# 08_FPGA.net
KiCad netlist of a schematic drawn in Altium Designer
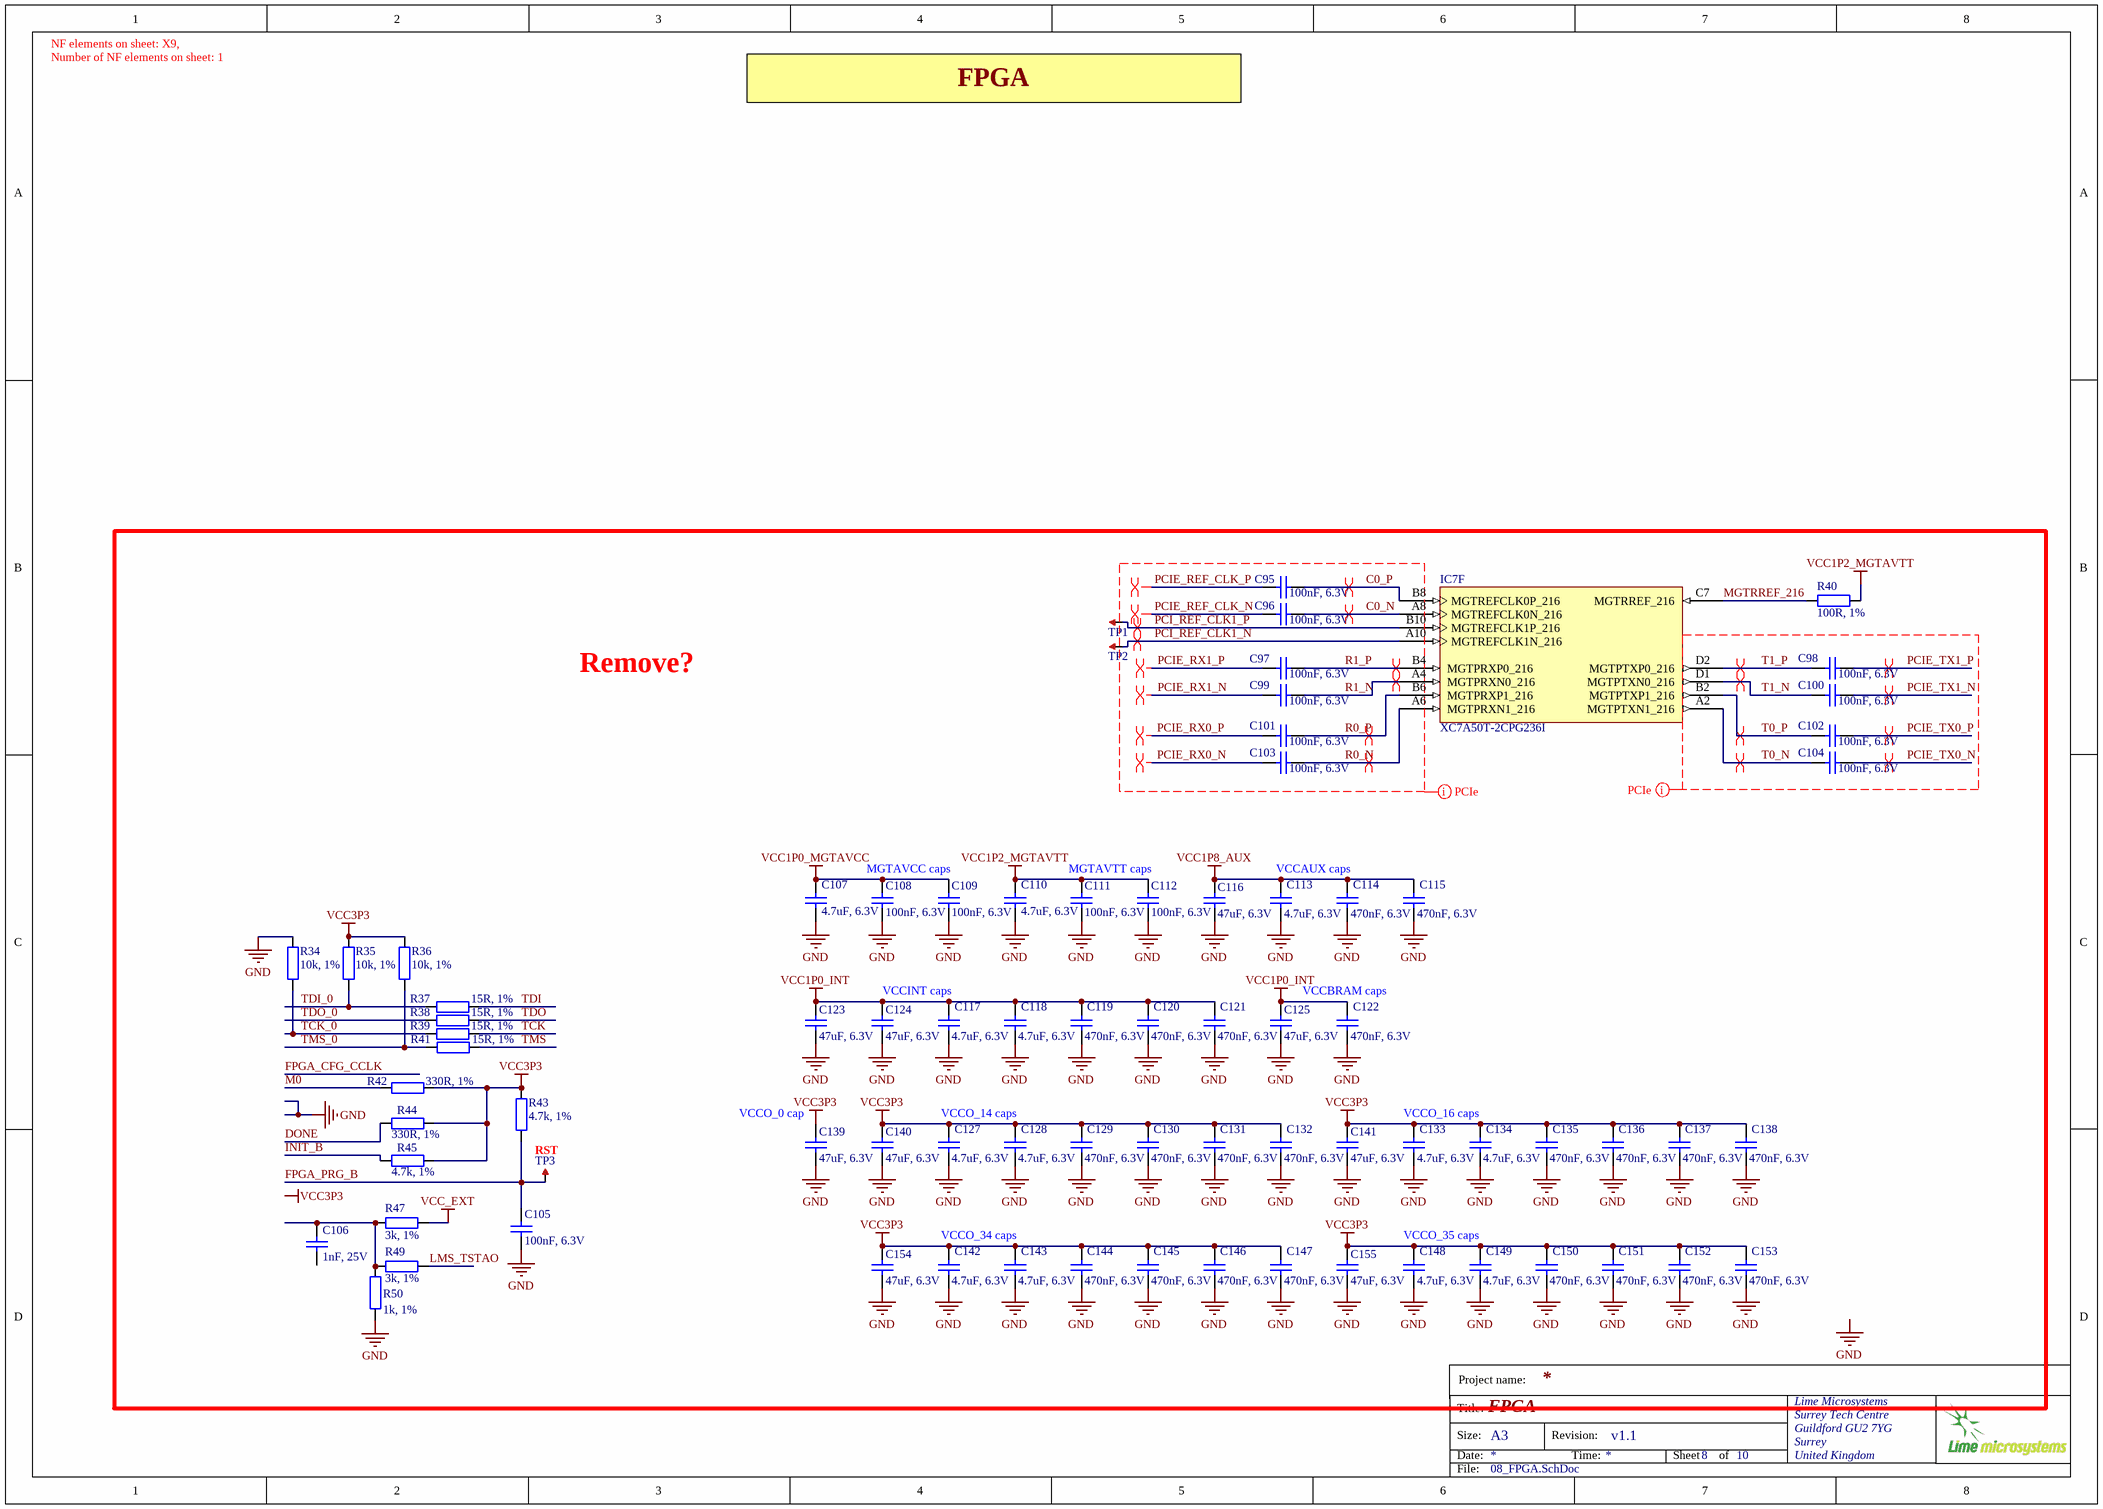
[diagram p0: 08_FPGA.SchDoc]

(export (version "E")
  (design (tool "Eeschema 10.0.6"))
  (components
    (comp (ref "C95")
      (value "100nF, 6.3V")
      (footprint "CAP0201")
      (fields (field (name "MANUFACTURER") "Samsung") (field (name "TOLERANCE") "20%"))
      (libsource (lib "LimeMicroAltiumLib_schLib") (part "Cap_0402"))
    )
    (comp (ref "C96")
      (value "100nF, 6.3V")
      (footprint "CAP0201")
      (fields (field (name "MANUFACTURER") "Samsung") (field (name "TOLERANCE") "20%"))
      (libsource (lib "LimeMicroAltiumLib_schLib") (part "Cap_0402"))
    )
    (comp (ref "C97")
      (value "100nF, 6.3V")
      (footprint "CAP0201")
      (fields (field (name "MANUFACTURER") "Samsung") (field (name "TOLERANCE") "20%"))
      (libsource (lib "LimeMicroAltiumLib_schLib") (part "Cap_0402"))
    )
    (comp (ref "C98")
      (value "100nF, 6.3V")
      (footprint "CAP0201")
      (fields (field (name "MANUFACTURER") "Samsung") (field (name "TOLERANCE") "20%"))
      (libsource (lib "LimeMicroAltiumLib_schLib") (part "Cap_0402"))
    )
    (comp (ref "C99")
      (value "100nF, 6.3V")
      (footprint "CAP0201")
      (fields (field (name "MANUFACTURER") "Samsung") (field (name "TOLERANCE") "20%"))
      (libsource (lib "LimeMicroAltiumLib_schLib") (part "Cap_0402"))
    )
    (comp (ref "C100")
      (value "100nF, 6.3V")
      (footprint "CAP0201")
      (fields (field (name "MANUFACTURER") "Samsung") (field (name "TOLERANCE") "20%"))
      (libsource (lib "LimeMicroAltiumLib_schLib") (part "Cap_0402"))
    )
    (comp (ref "C101")
      (value "100nF, 6.3V")
      (footprint "CAP0201")
      (fields (field (name "MANUFACTURER") "Samsung") (field (name "TOLERANCE") "20%"))
      (libsource (lib "LimeMicroAltiumLib_schLib") (part "Cap_0402"))
    )
    (comp (ref "C102")
      (value "100nF, 6.3V")
      (footprint "CAP0201")
      (fields (field (name "MANUFACTURER") "Samsung") (field (name "TOLERANCE") "20%"))
      (libsource (lib "LimeMicroAltiumLib_schLib") (part "Cap_0402"))
    )
    (comp (ref "C103")
      (value "100nF, 6.3V")
      (footprint "CAP0201")
      (fields (field (name "MANUFACTURER") "Samsung") (field (name "TOLERANCE") "20%"))
      (libsource (lib "LimeMicroAltiumLib_schLib") (part "Cap_0402"))
    )
    (comp (ref "C104")
      (value "100nF, 6.3V")
      (footprint "CAP0201")
      (fields (field (name "MANUFACTURER") "Samsung") (field (name "TOLERANCE") "20%"))
      (libsource (lib "LimeMicroAltiumLib_schLib") (part "Cap_0402"))
    )
    (comp (ref "C105")
      (value "100nF, 6.3V")
      (footprint "CAP0201")
      (fields (field (name "MANUFACTURER") "Samsung") (field (name "TOLERANCE") "20%"))
      (libsource (lib "LimeMicroAltiumLib_schLib") (part "Cap_0402"))
    )
    (comp (ref "C106")
      (value "1nF, 25V")
      (footprint "CAP0201")
      (fields (field (name "TOLERANCE") "±10%") (field (name "MANUFACTURER") "TDK Corporation"))
      (libsource (lib "LimeMicroAltiumLib_schLib") (part "Cap_0402"))
    )
    (comp (ref "C107")
      (value "4.7uF, 6.3V")
      (footprint "CAP0402")
      (fields
        (field (name "MANUFACTURER") "Murata Electronics North America")
        (field (name "TOLERANCE") "±20%")
      )
      (libsource (lib "LimeMicroAltiumLib_schLib") (part "Cap_0402"))
    )
    (comp (ref "C108")
      (value "100nF, 6.3V")
      (footprint "CAP0201")
      (fields (field (name "MANUFACTURER") "Samsung") (field (name "TOLERANCE") "20%"))
      (libsource (lib "LimeMicroAltiumLib_schLib") (part "Cap_0402"))
    )
    (comp (ref "C109")
      (value "100nF, 6.3V")
      (footprint "CAP0201")
      (fields (field (name "MANUFACTURER") "Samsung") (field (name "TOLERANCE") "20%"))
      (libsource (lib "LimeMicroAltiumLib_schLib") (part "Cap_0402"))
    )
    (comp (ref "C110")
      (value "4.7uF, 6.3V")
      (footprint "CAP0402")
      (fields
        (field (name "MANUFACTURER") "Murata Electronics North America")
        (field (name "TOLERANCE") "±20%")
      )
      (libsource (lib "LimeMicroAltiumLib_schLib") (part "Cap_0402"))
    )
    (comp (ref "C111")
      (value "100nF, 6.3V")
      (footprint "CAP0201")
      (fields (field (name "MANUFACTURER") "Samsung") (field (name "TOLERANCE") "20%"))
      (libsource (lib "LimeMicroAltiumLib_schLib") (part "Cap_0402"))
    )
    (comp (ref "C112")
      (value "100nF, 6.3V")
      (footprint "CAP0201")
      (fields (field (name "MANUFACTURER") "Samsung") (field (name "TOLERANCE") "20%"))
      (libsource (lib "LimeMicroAltiumLib_schLib") (part "Cap_0402"))
    )
    (comp (ref "C113")
      (value "4.7uF, 6.3V")
      (footprint "CAP0402")
      (fields
        (field (name "MANUFACTURER") "Murata Electronics North America")
        (field (name "TOLERANCE") "±20%")
      )
      (libsource (lib "LimeMicroAltiumLib_schLib") (part "Cap_0402"))
    )
    (comp (ref "C114")
      (value "470nF, 6.3V")
      (footprint "CAP0201")
      (fields (field (name "MANUFACTURER") "Murata") (field (name "TOLERANCE") "10%"))
      (libsource (lib "LimeMicroAltiumLib_schLib") (part "Cap_0402"))
    )
    (comp (ref "C115")
      (value "470nF, 6.3V")
      (footprint "CAP0201")
      (fields (field (name "MANUFACTURER") "Murata") (field (name "TOLERANCE") "10%"))
      (libsource (lib "LimeMicroAltiumLib_schLib") (part "Cap_0402"))
    )
    (comp (ref "C116")
      (value "47uF, 6.3V")
      (footprint "CAP0603")
      (fields (field (name "MANUFACTURER") "Murata") (field (name "TOLERANCE") "20%"))
      (libsource (lib "LimeFPGAboard_schLib") (part "Cap_0603"))
    )
    (comp (ref "C117")
      (value "4.7uF, 6.3V")
      (footprint "CAP0402")
      (fields
        (field (name "MANUFACTURER") "Murata Electronics North America")
        (field (name "TOLERANCE") "±20%")
      )
      (libsource (lib "LimeMicroAltiumLib_schLib") (part "Cap_0402"))
    )
    (comp (ref "C118")
      (value "4.7uF, 6.3V")
      (footprint "CAP0402")
      (fields
        (field (name "MANUFACTURER") "Murata Electronics North America")
        (field (name "TOLERANCE") "±20%")
      )
      (libsource (lib "LimeMicroAltiumLib_schLib") (part "Cap_0402"))
    )
    (comp (ref "C119")
      (value "470nF, 6.3V")
      (footprint "CAP0201")
      (fields (field (name "MANUFACTURER") "Murata") (field (name "TOLERANCE") "10%"))
      (libsource (lib "LimeMicroAltiumLib_schLib") (part "Cap_0402"))
    )
    (comp (ref "C120")
      (value "470nF, 6.3V")
      (footprint "CAP0201")
      (fields (field (name "MANUFACTURER") "Murata") (field (name "TOLERANCE") "10%"))
      (libsource (lib "LimeMicroAltiumLib_schLib") (part "Cap_0402"))
    )
    (comp (ref "C121")
      (value "470nF, 6.3V")
      (footprint "CAP0201")
      (fields (field (name "MANUFACTURER") "Murata") (field (name "TOLERANCE") "10%"))
      (libsource (lib "LimeMicroAltiumLib_schLib") (part "Cap_0402"))
    )
    (comp (ref "C122")
      (value "470nF, 6.3V")
      (footprint "CAP0201")
      (fields (field (name "MANUFACTURER") "Murata") (field (name "TOLERANCE") "10%"))
      (libsource (lib "LimeMicroAltiumLib_schLib") (part "Cap_0402"))
    )
    (comp (ref "C123")
      (value "47uF, 6.3V")
      (footprint "CAP0603")
      (fields (field (name "MANUFACTURER") "Murata") (field (name "TOLERANCE") "20%"))
      (libsource (lib "LimeFPGAboard_schLib") (part "Cap_0603"))
    )
    (comp (ref "C124")
      (value "47uF, 6.3V")
      (footprint "CAP0603")
      (fields (field (name "MANUFACTURER") "Murata") (field (name "TOLERANCE") "20%"))
      (libsource (lib "LimeFPGAboard_schLib") (part "Cap_0603"))
    )
    (comp (ref "C125")
      (value "47uF, 6.3V")
      (footprint "CAP0603")
      (fields (field (name "MANUFACTURER") "Murata") (field (name "TOLERANCE") "20%"))
      (libsource (lib "LimeFPGAboard_schLib") (part "Cap_0603"))
    )
    (comp (ref "C127")
      (value "4.7uF, 6.3V")
      (footprint "CAP0402")
      (fields
        (field (name "MANUFACTURER") "Murata Electronics North America")
        (field (name "TOLERANCE") "±20%")
      )
      (libsource (lib "LimeMicroAltiumLib_schLib") (part "Cap_0402"))
    )
    (comp (ref "C128")
      (value "4.7uF, 6.3V")
      (footprint "CAP0402")
      (fields
        (field (name "MANUFACTURER") "Murata Electronics North America")
        (field (name "TOLERANCE") "±20%")
      )
      (libsource (lib "LimeMicroAltiumLib_schLib") (part "Cap_0402"))
    )
    (comp (ref "C129")
      (value "470nF, 6.3V")
      (footprint "CAP0201")
      (fields (field (name "MANUFACTURER") "Murata") (field (name "TOLERANCE") "10%"))
      (libsource (lib "LimeMicroAltiumLib_schLib") (part "Cap_0402"))
    )
    (comp (ref "C130")
      (value "470nF, 6.3V")
      (footprint "CAP0201")
      (fields (field (name "MANUFACTURER") "Murata") (field (name "TOLERANCE") "10%"))
      (libsource (lib "LimeMicroAltiumLib_schLib") (part "Cap_0402"))
    )
    (comp (ref "C131")
      (value "470nF, 6.3V")
      (footprint "CAP0201")
      (fields (field (name "MANUFACTURER") "Murata") (field (name "TOLERANCE") "10%"))
      (libsource (lib "LimeMicroAltiumLib_schLib") (part "Cap_0402"))
    )
    (comp (ref "C132")
      (value "470nF, 6.3V")
      (footprint "CAP0201")
      (fields (field (name "MANUFACTURER") "Murata") (field (name "TOLERANCE") "10%"))
      (libsource (lib "LimeMicroAltiumLib_schLib") (part "Cap_0402"))
    )
    (comp (ref "C133")
      (value "4.7uF, 6.3V")
      (footprint "CAP0402")
      (fields
        (field (name "MANUFACTURER") "Murata Electronics North America")
        (field (name "TOLERANCE") "±20%")
      )
      (libsource (lib "LimeMicroAltiumLib_schLib") (part "Cap_0402"))
    )
    (comp (ref "C134")
      (value "4.7uF, 6.3V")
      (footprint "CAP0402")
      (fields
        (field (name "MANUFACTURER") "Murata Electronics North America")
        (field (name "TOLERANCE") "±20%")
      )
      (libsource (lib "LimeMicroAltiumLib_schLib") (part "Cap_0402"))
    )
    (comp (ref "C135")
      (value "470nF, 6.3V")
      (footprint "CAP0201")
      (fields (field (name "MANUFACTURER") "Murata") (field (name "TOLERANCE") "10%"))
      (libsource (lib "LimeMicroAltiumLib_schLib") (part "Cap_0402"))
    )
    (comp (ref "C136")
      (value "470nF, 6.3V")
      (footprint "CAP0201")
      (fields (field (name "MANUFACTURER") "Murata") (field (name "TOLERANCE") "10%"))
      (libsource (lib "LimeMicroAltiumLib_schLib") (part "Cap_0402"))
    )
    (comp (ref "C137")
      (value "470nF, 6.3V")
      (footprint "CAP0201")
      (fields (field (name "MANUFACTURER") "Murata") (field (name "TOLERANCE") "10%"))
      (libsource (lib "LimeMicroAltiumLib_schLib") (part "Cap_0402"))
    )
    (comp (ref "C138")
      (value "470nF, 6.3V")
      (footprint "CAP0201")
      (fields (field (name "MANUFACTURER") "Murata") (field (name "TOLERANCE") "10%"))
      (libsource (lib "LimeMicroAltiumLib_schLib") (part "Cap_0402"))
    )
    (comp (ref "C139")
      (value "47uF, 6.3V")
      (footprint "CAP0603")
      (fields (field (name "MANUFACTURER") "Murata") (field (name "TOLERANCE") "20%"))
      (libsource (lib "LimeFPGAboard_schLib") (part "Cap_0603"))
    )
    (comp (ref "C140")
      (value "47uF, 6.3V")
      (footprint "CAP0603")
      (fields (field (name "MANUFACTURER") "Murata") (field (name "TOLERANCE") "20%"))
      (libsource (lib "LimeFPGAboard_schLib") (part "Cap_0603"))
    )
    (comp (ref "C141")
      (value "47uF, 6.3V")
      (footprint "CAP0603")
      (fields (field (name "MANUFACTURER") "Murata") (field (name "TOLERANCE") "20%"))
      (libsource (lib "LimeFPGAboard_schLib") (part "Cap_0603"))
    )
    (comp (ref "C142")
      (value "4.7uF, 6.3V")
      (footprint "CAP0402")
      (fields
        (field (name "MANUFACTURER") "Murata Electronics North America")
        (field (name "TOLERANCE") "±20%")
      )
      (libsource (lib "LimeMicroAltiumLib_schLib") (part "Cap_0402"))
    )
    (comp (ref "C143")
      (value "4.7uF, 6.3V")
      (footprint "CAP0402")
      (fields
        (field (name "MANUFACTURER") "Murata Electronics North America")
        (field (name "TOLERANCE") "±20%")
      )
      (libsource (lib "LimeMicroAltiumLib_schLib") (part "Cap_0402"))
    )
    (comp (ref "C144")
      (value "470nF, 6.3V")
      (footprint "CAP0201")
      (fields (field (name "MANUFACTURER") "Murata") (field (name "TOLERANCE") "10%"))
      (libsource (lib "LimeMicroAltiumLib_schLib") (part "Cap_0402"))
    )
    (comp (ref "C145")
      (value "470nF, 6.3V")
      (footprint "CAP0201")
      (fields (field (name "MANUFACTURER") "Murata") (field (name "TOLERANCE") "10%"))
      (libsource (lib "LimeMicroAltiumLib_schLib") (part "Cap_0402"))
    )
    (comp (ref "C146")
      (value "470nF, 6.3V")
      (footprint "CAP0201")
      (fields (field (name "MANUFACTURER") "Murata") (field (name "TOLERANCE") "10%"))
      (libsource (lib "LimeMicroAltiumLib_schLib") (part "Cap_0402"))
    )
    (comp (ref "C147")
      (value "470nF, 6.3V")
      (footprint "CAP0201")
      (fields (field (name "MANUFACTURER") "Murata") (field (name "TOLERANCE") "10%"))
      (libsource (lib "LimeMicroAltiumLib_schLib") (part "Cap_0402"))
    )
    (comp (ref "C148")
      (value "4.7uF, 6.3V")
      (footprint "CAP0402")
      (fields
        (field (name "MANUFACTURER") "Murata Electronics North America")
        (field (name "TOLERANCE") "±20%")
      )
      (libsource (lib "LimeMicroAltiumLib_schLib") (part "Cap_0402"))
    )
    (comp (ref "C149")
      (value "4.7uF, 6.3V")
      (footprint "CAP0402")
      (fields
        (field (name "MANUFACTURER") "Murata Electronics North America")
        (field (name "TOLERANCE") "±20%")
      )
      (libsource (lib "LimeMicroAltiumLib_schLib") (part "Cap_0402"))
    )
    (comp (ref "C150")
      (value "470nF, 6.3V")
      (footprint "CAP0201")
      (fields (field (name "MANUFACTURER") "Murata") (field (name "TOLERANCE") "10%"))
      (libsource (lib "LimeMicroAltiumLib_schLib") (part "Cap_0402"))
    )
    (comp (ref "C151")
      (value "470nF, 6.3V")
      (footprint "CAP0201")
      (fields (field (name "MANUFACTURER") "Murata") (field (name "TOLERANCE") "10%"))
      (libsource (lib "LimeMicroAltiumLib_schLib") (part "Cap_0402"))
    )
    (comp (ref "C152")
      (value "470nF, 6.3V")
      (footprint "CAP0201")
      (fields (field (name "MANUFACTURER") "Murata") (field (name "TOLERANCE") "10%"))
      (libsource (lib "LimeMicroAltiumLib_schLib") (part "Cap_0402"))
    )
    (comp (ref "C153")
      (value "470nF, 6.3V")
      (footprint "CAP0201")
      (fields (field (name "MANUFACTURER") "Murata") (field (name "TOLERANCE") "10%"))
      (libsource (lib "LimeMicroAltiumLib_schLib") (part "Cap_0402"))
    )
    (comp (ref "C154")
      (value "47uF, 6.3V")
      (footprint "CAP0603")
      (fields (field (name "MANUFACTURER") "Murata") (field (name "TOLERANCE") "20%"))
      (libsource (lib "LimeFPGAboard_schLib") (part "Cap_0603"))
    )
    (comp (ref "C155")
      (value "47uF, 6.3V")
      (footprint "CAP0603")
      (fields (field (name "MANUFACTURER") "Murata") (field (name "TOLERANCE") "20%"))
      (libsource (lib "LimeFPGAboard_schLib") (part "Cap_0603"))
    )
    (comp (ref "IC7")
      (value "XC7A50T-2CPG236I")
      (footprint "XC7A35T-2CPG236")
      (description "Artix-7 FPGA")
      (fields (field (name "MANUFACTURER") "Xilinx"))
      (libsource (lib "LimeMicroAltiumLib_schLib_r04") (part "XC7A35T-2CPG236"))
    )
    (comp (ref "R34")
      (value "10k, 1%")
      (footprint "RES0201")
      (fields (field (name "MANUFACTURER") "Yageo") (field (name "TOLERANCE") "1%"))
      (libsource (lib "LimeFPGAboard_schLib") (part "Res_0402"))
    )
    (comp (ref "R35")
      (value "10k, 1%")
      (footprint "RES0201")
      (fields (field (name "MANUFACTURER") "Yageo") (field (name "TOLERANCE") "1%"))
      (libsource (lib "LimeFPGAboard_schLib") (part "Res_0402"))
    )
    (comp (ref "R36")
      (value "10k, 1%")
      (footprint "RES0201")
      (fields (field (name "MANUFACTURER") "Yageo") (field (name "TOLERANCE") "1%"))
      (libsource (lib "LimeFPGAboard_schLib") (part "Res_0402"))
    )
    (comp (ref "R37")
      (value "15R, 1%")
      (footprint "RES0201")
      (fields (field (name "MANUFACTURER") "Yageo") (field (name "TOLERANCE") "1%"))
      (libsource (lib "LimeFPGAboard_schLib") (part "Res_0402"))
    )
    (comp (ref "R38")
      (value "15R, 1%")
      (footprint "RES0201")
      (fields (field (name "MANUFACTURER") "Yageo") (field (name "TOLERANCE") "1%"))
      (libsource (lib "LimeFPGAboard_schLib") (part "Res_0402"))
    )
    (comp (ref "R39")
      (value "15R, 1%")
      (footprint "RES0201")
      (fields (field (name "MANUFACTURER") "Yageo") (field (name "TOLERANCE") "1%"))
      (libsource (lib "LimeFPGAboard_schLib") (part "Res_0402"))
    )
    (comp (ref "R40")
      (value "100R, 1%")
      (footprint "RES0201")
      (fields (field (name "MANUFACTURER") "Yageo") (field (name "TOLERANCE") "1%"))
      (libsource (lib "LimeFPGAboard_schLib") (part "Res_0402"))
    )
    (comp (ref "R41")
      (value "15R, 1%")
      (footprint "RES0201")
      (fields (field (name "MANUFACTURER") "Yageo") (field (name "TOLERANCE") "1%"))
      (libsource (lib "LimeFPGAboard_schLib") (part "Res_0402"))
    )
    (comp (ref "R42")
      (value "330R, 1%")
      (footprint "RES0201")
      (fields (field (name "MANUFACTURER") "Vishay Dale") (field (name "TOLERANCE") "1%"))
      (libsource (lib "LimeFPGAboard_schLib") (part "Res_0402"))
    )
    (comp (ref "R43")
      (value "4.7k, 1%")
      (footprint "RES0201")
      (fields (field (name "MANUFACTURER") "Yageo") (field (name "TOLERANCE") "1%"))
      (libsource (lib "LimeFPGAboard_schLib") (part "Res_0402"))
    )
    (comp (ref "R44")
      (value "330R, 1%")
      (footprint "RES0201")
      (fields (field (name "MANUFACTURER") "Vishay Dale") (field (name "TOLERANCE") "1%"))
      (libsource (lib "LimeFPGAboard_schLib") (part "Res_0402"))
    )
    (comp (ref "R45")
      (value "4.7k, 1%")
      (footprint "RES0201")
      (fields (field (name "MANUFACTURER") "Yageo") (field (name "TOLERANCE") "1%"))
      (libsource (lib "LimeFPGAboard_schLib") (part "Res_0402"))
    )
    (comp (ref "R47")
      (value "3k, 1%")
      (footprint "RES0201")
      (fields (field (name "MANUFACTURER") "Yageo") (field (name "TOLERANCE") "1%"))
      (libsource (lib "LimeFPGAboard_schLib") (part "Res_0402"))
    )
    (comp (ref "R49")
      (value "3k, 1%")
      (footprint "RES0201")
      (fields (field (name "MANUFACTURER") "Yageo") (field (name "TOLERANCE") "1%"))
      (libsource (lib "LimeFPGAboard_schLib") (part "Res_0402"))
    )
    (comp (ref "R50")
      (value "1k, 1%")
      (footprint "RES0201")
      (fields (field (name "MANUFACTURER") "Yageo") (field (name "TOLERANCE") "1%"))
      (libsource (lib "LimeMicroAltiumLib_schLib") (part "Res_0402"))
    )
    (comp (ref "TP1")
      (value "TESTPOINT_PAD")
      (footprint "TP_PAD_1MM")
      (description "Test Point PCB mount Miniature White")
      (libsource (lib "LimeMicroAltiumLib_schLib_r04") (part "TESTPOINT_PAD"))
    )
    (comp (ref "TP2")
      (value "TESTPOINT_PAD")
      (footprint "TP_PAD_1MM")
      (description "Test Point PCB mount Miniature White")
      (libsource (lib "LimeMicroAltiumLib_schLib_r04") (part "TESTPOINT_PAD"))
    )
    (comp (ref "TP3")
      (value "TESTPOINT_PAD")
      (footprint "TP_PAD_1MM")
      (description "Test Point PCB mount Miniature White")
      (libsource (lib "LimeMicroAltiumLib_schLib_r04") (part "TESTPOINT_PAD"))
    )
  )
  (nets
    (net (code "1") (name "/C0_N") (class "Default")
      (node (ref "C96") (pin "2") (pinfunction "2_2") (pintype "passive"))
      (node (ref "IC7") (pin "A8") (pinfunction "MGTREFCLK0N_216_A8") (pintype "input"))
    )
    (net (code "2") (name "/C0_P") (class "Default")
      (node (ref "C95") (pin "2") (pinfunction "2_2") (pintype "passive"))
      (node (ref "IC7") (pin "B8") (pinfunction "MGTREFCLK0P_216_B8") (pintype "input"))
    )
    (net (code "3") (name "/DONE") (class "Default")
      (node (ref "R44") (pin "2") (pinfunction "2_2") (pintype "passive"))
    )
    (net (code "5") (name "/FPGA_PRG_B") (class "Default")
      (node (ref "C105") (pin "1") (pinfunction "1_1") (pintype "passive"))
      (node (ref "R43") (pin "2") (pinfunction "2_2") (pintype "passive"))
      (node (ref "TP3") (pin "1") (pintype "passive"))
    )
    (net (code "6") (name "/INIT_B") (class "Default")
      (node (ref "R45") (pin "2") (pinfunction "2_2") (pintype "passive"))
    )
    (net (code "7") (name "/LMS_TSTAO") (class "Default")
      (node (ref "R49") (pin "2") (pinfunction "2_2") (pintype "passive"))
    )
    (net (code "8") (name "/M0") (class "Default")
      (node (ref "R42") (pin "2") (pinfunction "2_2") (pintype "passive"))
    )
    (net (code "9") (name "/MGTRREF_216") (class "Default")
      (node (ref "IC7") (pin "C7") (pinfunction "MGTRREF_216_C7") (pintype "input"))
      (node (ref "R40") (pin "2") (pinfunction "2_2") (pintype "passive"))
    )
    (net (code "10") (name "/PCIE_REF_CLK_N") (class "Default")
      (node (ref "C96") (pin "1") (pinfunction "1_1") (pintype "passive"))
    )
    (net (code "11") (name "/PCIE_REF_CLK_P") (class "Default")
      (node (ref "C95") (pin "1") (pinfunction "1_1") (pintype "passive"))
    )
    (net (code "12") (name "/PCIE_RX0_N") (class "Default")
      (node (ref "C103") (pin "1") (pinfunction "1_1") (pintype "passive"))
    )
    (net (code "13") (name "/PCIE_RX0_P") (class "Default")
      (node (ref "C101") (pin "1") (pinfunction "1_1") (pintype "passive"))
    )
    (net (code "14") (name "/PCIE_RX1_N") (class "Default")
      (node (ref "C99") (pin "1") (pinfunction "1_1") (pintype "passive"))
    )
    (net (code "15") (name "/PCIE_RX1_P") (class "Default")
      (node (ref "C97") (pin "1") (pinfunction "1_1") (pintype "passive"))
    )
    (net (code "16") (name "/PCIE_TX0_N") (class "Default")
      (node (ref "C104") (pin "2") (pinfunction "2_2") (pintype "passive"))
    )
    (net (code "17") (name "/PCIE_TX0_P") (class "Default")
      (node (ref "C102") (pin "2") (pinfunction "2_2") (pintype "passive"))
    )
    (net (code "18") (name "/PCIE_TX1_N") (class "Default")
      (node (ref "C100") (pin "2") (pinfunction "2_2") (pintype "passive"))
    )
    (net (code "19") (name "/PCIE_TX1_P") (class "Default")
      (node (ref "C98") (pin "2") (pinfunction "2_2") (pintype "passive"))
    )
    (net (code "20") (name "/PCI_REF_CLK1_N") (class "Default")
      (node (ref "IC7") (pin "A10") (pinfunction "MGTREFCLK1N_216_A10") (pintype "input"))
      (node (ref "TP2") (pin "1") (pintype "passive"))
    )
    (net (code "21") (name "/PCI_REF_CLK1_P") (class "Default")
      (node (ref "IC7") (pin "B10") (pinfunction "MGTREFCLK1P_216_B10") (pintype "input"))
      (node (ref "TP1") (pin "1") (pintype "passive"))
    )
    (net (code "22") (name "/R0_N") (class "Default")
      (node (ref "C103") (pin "2") (pinfunction "2_2") (pintype "passive"))
      (node (ref "IC7") (pin "A6") (pinfunction "MGTPRXN1_216_A6") (pintype "input"))
    )
    (net (code "23") (name "/R0_P") (class "Default")
      (node (ref "C101") (pin "2") (pinfunction "2_2") (pintype "passive"))
      (node (ref "IC7") (pin "B6") (pinfunction "MGTPRXP1_216_B6") (pintype "input"))
    )
    (net (code "24") (name "/R1_N") (class "Default")
      (node (ref "C99") (pin "2") (pinfunction "2_2") (pintype "passive"))
      (node (ref "IC7") (pin "A4") (pinfunction "MGTPRXN0_216_A4") (pintype "input"))
    )
    (net (code "25") (name "/R1_P") (class "Default")
      (node (ref "C97") (pin "2") (pinfunction "2_2") (pintype "passive"))
      (node (ref "IC7") (pin "B4") (pinfunction "MGTPRXP0_216_B4") (pintype "input"))
    )
    (net (code "26") (name "/T0_N") (class "Default")
      (node (ref "C104") (pin "1") (pinfunction "1_1") (pintype "passive"))
      (node (ref "IC7") (pin "A2") (pinfunction "MGTPTXN1_216_A2") (pintype "output"))
    )
    (net (code "27") (name "/T0_P") (class "Default")
      (node (ref "C102") (pin "1") (pinfunction "1_1") (pintype "passive"))
      (node (ref "IC7") (pin "B2") (pinfunction "MGTPTXP1_216_B2") (pintype "output"))
    )
    (net (code "28") (name "/T1_N") (class "Default")
      (node (ref "C100") (pin "1") (pinfunction "1_1") (pintype "passive"))
      (node (ref "IC7") (pin "D1") (pinfunction "MGTPTXN0_216_D1") (pintype "output"))
    )
    (net (code "29") (name "/T1_P") (class "Default")
      (node (ref "C98") (pin "1") (pinfunction "1_1") (pintype "passive"))
      (node (ref "IC7") (pin "D2") (pinfunction "MGTPTXP0_216_D2") (pintype "output"))
    )
    (net (code "30") (name "/TCK") (class "Default")
      (node (ref "R39") (pin "1") (pinfunction "1_1") (pintype "passive"))
    )
    (net (code "31") (name "/TCK_0") (class "Default")
      (node (ref "R34") (pin "2") (pinfunction "2_2") (pintype "passive"))
      (node (ref "R39") (pin "2") (pinfunction "2_2") (pintype "passive"))
    )
    (net (code "32") (name "/TDI") (class "Default")
      (node (ref "R37") (pin "1") (pinfunction "1_1") (pintype "passive"))
    )
    (net (code "33") (name "/TDI_0") (class "Default")
      (node (ref "R35") (pin "2") (pinfunction "2_2") (pintype "passive"))
      (node (ref "R37") (pin "2") (pinfunction "2_2") (pintype "passive"))
    )
    (net (code "34") (name "/TDO") (class "Default")
      (node (ref "R38") (pin "1") (pinfunction "1_1") (pintype "passive"))
    )
    (net (code "35") (name "/TDO_0") (class "Default")
      (node (ref "R38") (pin "2") (pinfunction "2_2") (pintype "passive"))
    )
    (net (code "36") (name "/TMS") (class "Default")
      (node (ref "R41") (pin "1") (pinfunction "1_1") (pintype "passive"))
    )
    (net (code "37") (name "/TMS_0") (class "Default")
      (node (ref "R36") (pin "2") (pinfunction "2_2") (pintype "passive"))
      (node (ref "R41") (pin "2") (pinfunction "2_2") (pintype "passive"))
    )
    (net (code "38") (name "GND") (class "Default")
      (node (ref "C105") (pin "2") (pinfunction "2_2") (pintype "passive"))
      (node (ref "C107") (pin "1") (pinfunction "1_1") (pintype "passive"))
      (node (ref "C108") (pin "2") (pinfunction "2_2") (pintype "passive"))
      (node (ref "C109") (pin "2") (pinfunction "2_2") (pintype "passive"))
      (node (ref "C110") (pin "1") (pinfunction "1_1") (pintype "passive"))
      (node (ref "C111") (pin "2") (pinfunction "2_2") (pintype "passive"))
      (node (ref "C112") (pin "2") (pinfunction "2_2") (pintype "passive"))
      (node (ref "C113") (pin "1") (pinfunction "1_1") (pintype "passive"))
      (node (ref "C114") (pin "2") (pinfunction "2_2") (pintype "passive"))
      (node (ref "C115") (pin "2") (pinfunction "2_2") (pintype "passive"))
      (node (ref "C116") (pin "1") (pinfunction "1_1") (pintype "passive"))
      (node (ref "C117") (pin "1") (pinfunction "1_1") (pintype "passive"))
      (node (ref "C118") (pin "1") (pinfunction "1_1") (pintype "passive"))
      (node (ref "C119") (pin "2") (pinfunction "2_2") (pintype "passive"))
      (node (ref "C120") (pin "2") (pinfunction "2_2") (pintype "passive"))
      (node (ref "C121") (pin "2") (pinfunction "2_2") (pintype "passive"))
      (node (ref "C122") (pin "2") (pinfunction "2_2") (pintype "passive"))
      (node (ref "C123") (pin "1") (pinfunction "1_1") (pintype "passive"))
      (node (ref "C124") (pin "1") (pinfunction "1_1") (pintype "passive"))
      (node (ref "C125") (pin "1") (pinfunction "1_1") (pintype "passive"))
      (node (ref "C127") (pin "1") (pinfunction "1_1") (pintype "passive"))
      (node (ref "C128") (pin "1") (pinfunction "1_1") (pintype "passive"))
      (node (ref "C129") (pin "2") (pinfunction "2_2") (pintype "passive"))
      (node (ref "C130") (pin "2") (pinfunction "2_2") (pintype "passive"))
      (node (ref "C131") (pin "2") (pinfunction "2_2") (pintype "passive"))
      (node (ref "C132") (pin "2") (pinfunction "2_2") (pintype "passive"))
      (node (ref "C133") (pin "1") (pinfunction "1_1") (pintype "passive"))
      (node (ref "C134") (pin "1") (pinfunction "1_1") (pintype "passive"))
      (node (ref "C135") (pin "2") (pinfunction "2_2") (pintype "passive"))
      (node (ref "C136") (pin "2") (pinfunction "2_2") (pintype "passive"))
      (node (ref "C137") (pin "2") (pinfunction "2_2") (pintype "passive"))
      (node (ref "C138") (pin "2") (pinfunction "2_2") (pintype "passive"))
      (node (ref "C139") (pin "1") (pinfunction "1_1") (pintype "passive"))
      (node (ref "C140") (pin "1") (pinfunction "1_1") (pintype "passive"))
      (node (ref "C141") (pin "1") (pinfunction "1_1") (pintype "passive"))
      (node (ref "C142") (pin "1") (pinfunction "1_1") (pintype "passive"))
      (node (ref "C143") (pin "1") (pinfunction "1_1") (pintype "passive"))
      (node (ref "C144") (pin "2") (pinfunction "2_2") (pintype "passive"))
      (node (ref "C145") (pin "2") (pinfunction "2_2") (pintype "passive"))
      (node (ref "C146") (pin "2") (pinfunction "2_2") (pintype "passive"))
      (node (ref "C147") (pin "2") (pinfunction "2_2") (pintype "passive"))
      (node (ref "C148") (pin "1") (pinfunction "1_1") (pintype "passive"))
      (node (ref "C149") (pin "1") (pinfunction "1_1") (pintype "passive"))
      (node (ref "C150") (pin "2") (pinfunction "2_2") (pintype "passive"))
      (node (ref "C151") (pin "2") (pinfunction "2_2") (pintype "passive"))
      (node (ref "C152") (pin "2") (pinfunction "2_2") (pintype "passive"))
      (node (ref "C153") (pin "2") (pinfunction "2_2") (pintype "passive"))
      (node (ref "C154") (pin "1") (pinfunction "1_1") (pintype "passive"))
      (node (ref "C155") (pin "1") (pinfunction "1_1") (pintype "passive"))
      (node (ref "R34") (pin "1") (pinfunction "1_1") (pintype "passive"))
      (node (ref "R50") (pin "2") (pinfunction "2_2") (pintype "passive"))
    )
    (net (code "39") (name "Net-(C106-Pad1)") (class "Default")
      (node (ref "C106") (pin "1") (pinfunction "1_1") (pintype "passive"))
      (node (ref "R47") (pin "1") (pinfunction "1_1") (pintype "passive"))
      (node (ref "R49") (pin "1") (pinfunction "1_1") (pintype "passive"))
      (node (ref "R50") (pin "1") (pinfunction "1_1") (pintype "passive"))
    )
    (net (code "40") (name "VCC1P0_INT") (class "Default")
      (node (ref "C117") (pin "2") (pinfunction "2_2") (pintype "passive"))
      (node (ref "C118") (pin "2") (pinfunction "2_2") (pintype "passive"))
      (node (ref "C119") (pin "1") (pinfunction "1_1") (pintype "passive"))
      (node (ref "C120") (pin "1") (pinfunction "1_1") (pintype "passive"))
      (node (ref "C121") (pin "1") (pinfunction "1_1") (pintype "passive"))
      (node (ref "C122") (pin "1") (pinfunction "1_1") (pintype "passive"))
      (node (ref "C123") (pin "2") (pinfunction "2_2") (pintype "passive"))
      (node (ref "C124") (pin "2") (pinfunction "2_2") (pintype "passive"))
      (node (ref "C125") (pin "2") (pinfunction "2_2") (pintype "passive"))
    )
    (net (code "41") (name "VCC1P0_MGTAVCC") (class "Default")
      (node (ref "C107") (pin "2") (pinfunction "2_2") (pintype "passive"))
      (node (ref "C108") (pin "1") (pinfunction "1_1") (pintype "passive"))
      (node (ref "C109") (pin "1") (pinfunction "1_1") (pintype "passive"))
    )
    (net (code "42") (name "VCC1P2_MGTAVTT") (class "Default")
      (node (ref "C110") (pin "2") (pinfunction "2_2") (pintype "passive"))
      (node (ref "C111") (pin "1") (pinfunction "1_1") (pintype "passive"))
      (node (ref "C112") (pin "1") (pinfunction "1_1") (pintype "passive"))
      (node (ref "R40") (pin "1") (pinfunction "1_1") (pintype "passive"))
    )
    (net (code "43") (name "VCC1P8_AUX") (class "Default")
      (node (ref "C113") (pin "2") (pinfunction "2_2") (pintype "passive"))
      (node (ref "C114") (pin "1") (pinfunction "1_1") (pintype "passive"))
      (node (ref "C115") (pin "1") (pinfunction "1_1") (pintype "passive"))
      (node (ref "C116") (pin "2") (pinfunction "2_2") (pintype "passive"))
    )
    (net (code "44") (name "VCC3P3") (class "Default")
      (node (ref "C127") (pin "2") (pinfunction "2_2") (pintype "passive"))
      (node (ref "C128") (pin "2") (pinfunction "2_2") (pintype "passive"))
      (node (ref "C129") (pin "1") (pinfunction "1_1") (pintype "passive"))
      (node (ref "C130") (pin "1") (pinfunction "1_1") (pintype "passive"))
      (node (ref "C131") (pin "1") (pinfunction "1_1") (pintype "passive"))
      (node (ref "C132") (pin "1") (pinfunction "1_1") (pintype "passive"))
      (node (ref "C133") (pin "2") (pinfunction "2_2") (pintype "passive"))
      (node (ref "C134") (pin "2") (pinfunction "2_2") (pintype "passive"))
      (node (ref "C135") (pin "1") (pinfunction "1_1") (pintype "passive"))
      (node (ref "C136") (pin "1") (pinfunction "1_1") (pintype "passive"))
      (node (ref "C137") (pin "1") (pinfunction "1_1") (pintype "passive"))
      (node (ref "C138") (pin "1") (pinfunction "1_1") (pintype "passive"))
      (node (ref "C139") (pin "2") (pinfunction "2_2") (pintype "passive"))
      (node (ref "C140") (pin "2") (pinfunction "2_2") (pintype "passive"))
      (node (ref "C141") (pin "2") (pinfunction "2_2") (pintype "passive"))
      (node (ref "C142") (pin "2") (pinfunction "2_2") (pintype "passive"))
      (node (ref "C143") (pin "2") (pinfunction "2_2") (pintype "passive"))
      (node (ref "C144") (pin "1") (pinfunction "1_1") (pintype "passive"))
      (node (ref "C145") (pin "1") (pinfunction "1_1") (pintype "passive"))
      (node (ref "C146") (pin "1") (pinfunction "1_1") (pintype "passive"))
      (node (ref "C147") (pin "1") (pinfunction "1_1") (pintype "passive"))
      (node (ref "C148") (pin "2") (pinfunction "2_2") (pintype "passive"))
      (node (ref "C149") (pin "2") (pinfunction "2_2") (pintype "passive"))
      (node (ref "C150") (pin "1") (pinfunction "1_1") (pintype "passive"))
      (node (ref "C151") (pin "1") (pinfunction "1_1") (pintype "passive"))
      (node (ref "C152") (pin "1") (pinfunction "1_1") (pintype "passive"))
      (node (ref "C153") (pin "1") (pinfunction "1_1") (pintype "passive"))
      (node (ref "C154") (pin "2") (pinfunction "2_2") (pintype "passive"))
      (node (ref "C155") (pin "2") (pinfunction "2_2") (pintype "passive"))
      (node (ref "R35") (pin "1") (pinfunction "1_1") (pintype "passive"))
      (node (ref "R36") (pin "1") (pinfunction "1_1") (pintype "passive"))
      (node (ref "R42") (pin "1") (pinfunction "1_1") (pintype "passive"))
      (node (ref "R43") (pin "1") (pinfunction "1_1") (pintype "passive"))
      (node (ref "R44") (pin "1") (pinfunction "1_1") (pintype "passive"))
      (node (ref "R45") (pin "1") (pinfunction "1_1") (pintype "passive"))
    )
    (net (code "45") (name "VCC_EXT") (class "Default")
      (node (ref "R47") (pin "2") (pinfunction "2_2") (pintype "passive"))
    )
    (net (code "46") (name "unconnected-(C106-Pad2)") (class "Default")
      (node (ref "C106") (pin "2") (pinfunction "2_2") (pintype "passive"))
    )
  )
)
